# Generador_de_Funciones.net
KiCad netlist of a schematic drawn in EAGLE
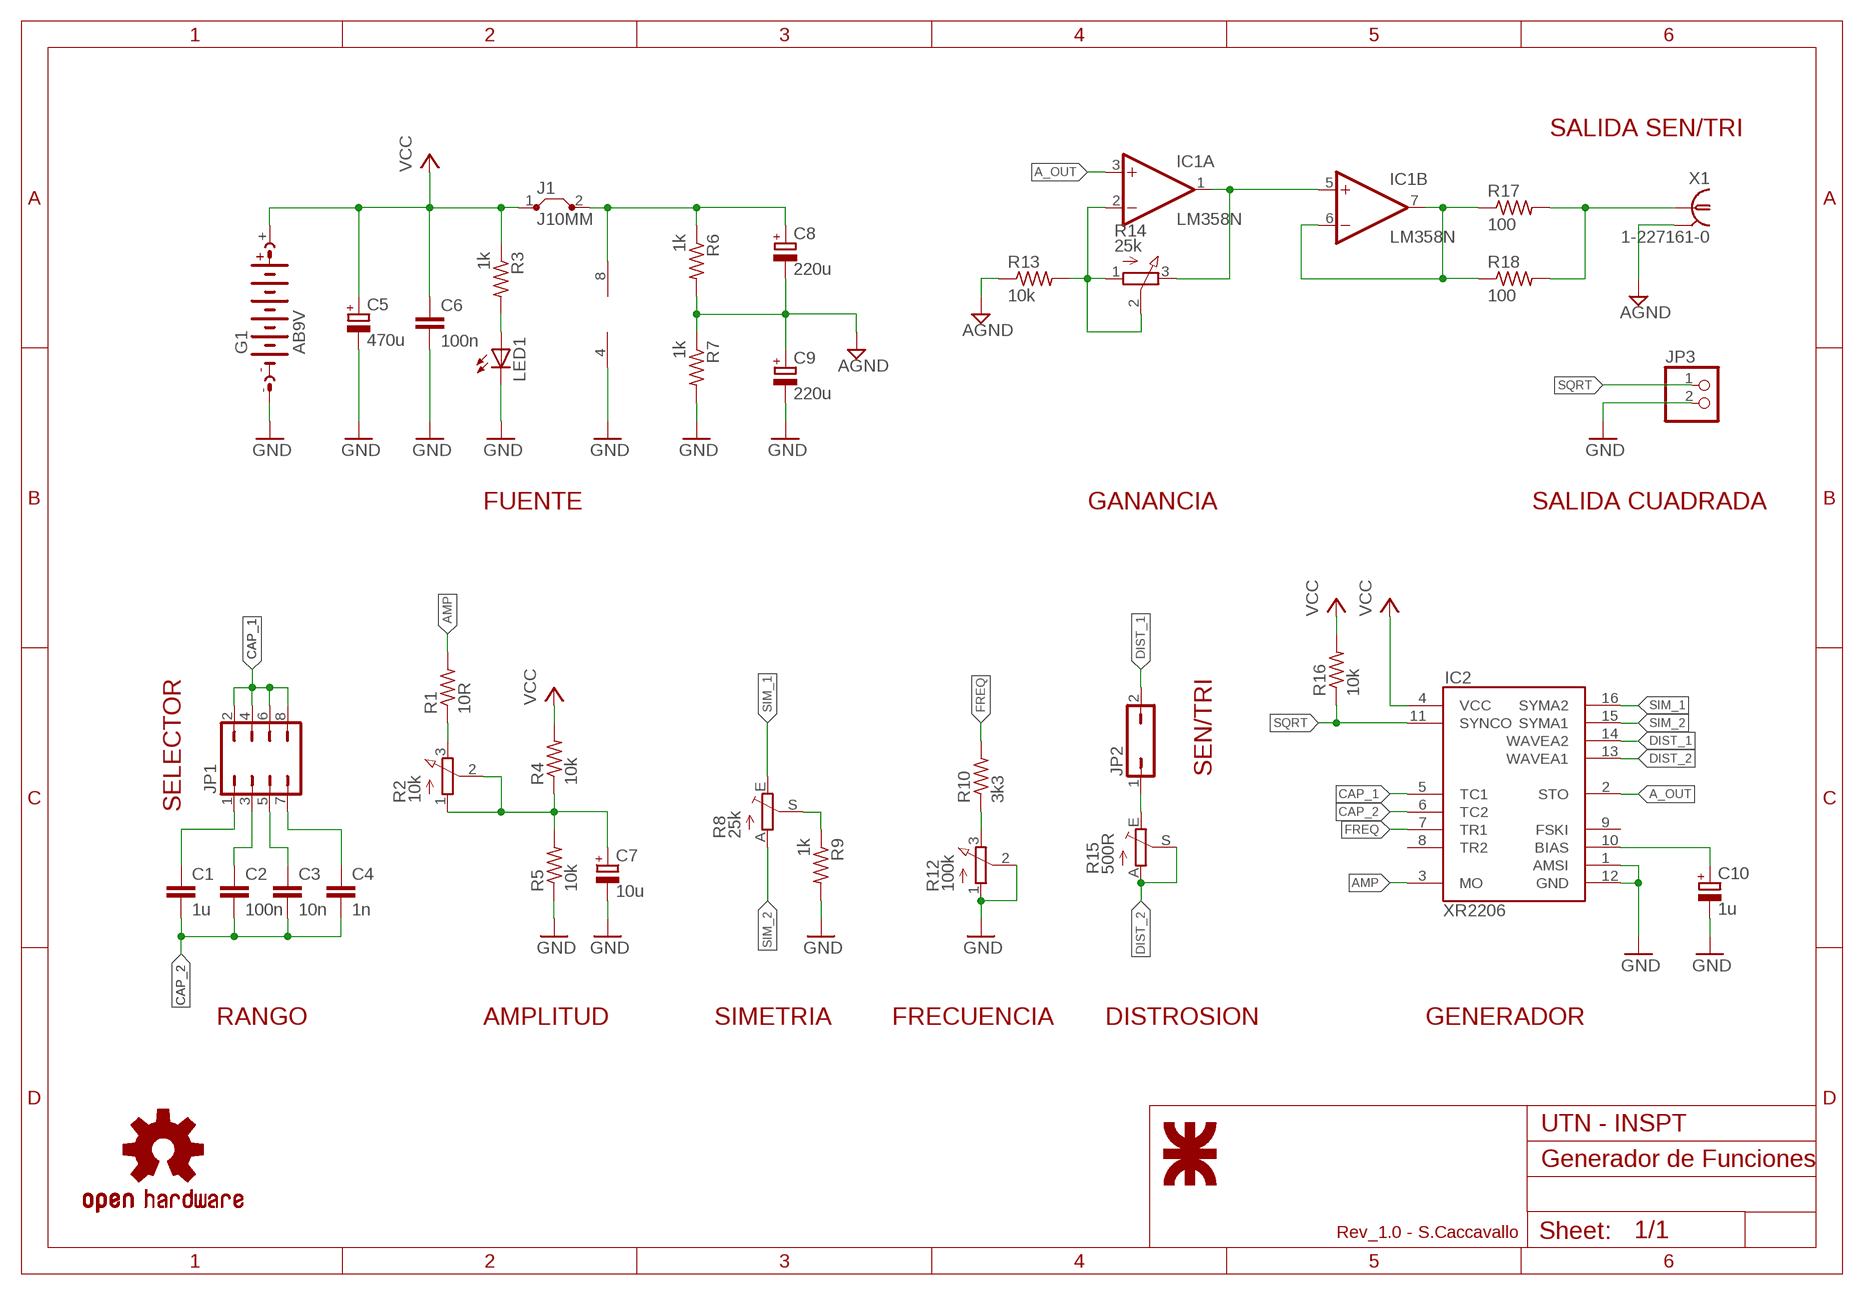
[diagram p0: schematic, sheet 1]

(export (version "E")
  (design (tool "Eeschema 10.0.6"))
  (components
    (comp (ref "C1")
      (value "1u")
      (footprint "eagle-import:C050-024X044")
      (libsource (lib "eagle-import") (part "C-EU050-024X044"))
    )
    (comp (ref "C2")
      (value "100n")
      (footprint "eagle-import:C050-024X044")
      (libsource (lib "eagle-import") (part "C-EU050-024X044"))
    )
    (comp (ref "C3")
      (value "10n")
      (footprint "eagle-import:C050-024X044")
      (libsource (lib "eagle-import") (part "C-EU050-024X044"))
    )
    (comp (ref "C4")
      (value "1n")
      (footprint "eagle-import:C050-024X044")
      (libsource (lib "eagle-import") (part "C-EU050-024X044"))
    )
    (comp (ref "C5")
      (value "470u")
      (footprint "eagle-import:E3,5-8")
      (libsource (lib "eagle-import") (part "CPOL-EUE3.5-8"))
    )
    (comp (ref "C6")
      (value "100n")
      (footprint "eagle-import:C050-024X044")
      (libsource (lib "eagle-import") (part "C-EU050-024X044"))
    )
    (comp (ref "C7")
      (value "10u")
      (footprint "eagle-import:E2,5-6")
      (libsource (lib "eagle-import") (part "CPOL-EUE2.5-6"))
    )
    (comp (ref "C8")
      (value "220u")
      (footprint "eagle-import:E3,5-8")
      (libsource (lib "eagle-import") (part "CPOL-EUE3.5-8"))
    )
    (comp (ref "C9")
      (value "220u")
      (footprint "eagle-import:E3,5-8")
      (libsource (lib "eagle-import") (part "CPOL-EUE3.5-8"))
    )
    (comp (ref "C10")
      (value "1u")
      (footprint "eagle-import:E2,5-6")
      (libsource (lib "eagle-import") (part "CPOL-EUE2.5-6"))
    )
    (comp (ref "G1")
      (value "AB9V")
      (footprint "eagle-import:AB9V")
      (libsource (lib "eagle-import") (part "AB9V"))
    )
    (comp (ref "IC1")
      (value "LM358N")
      (footprint "eagle-import:DIL08")
      (libsource (lib "eagle-import") (part "LM358N"))
    )
    (comp (ref "IC2")
      (value "XR2206")
      (footprint "eagle-import:DIL16")
      (libsource (lib "eagle-import") (part "XR2206"))
    )
    (comp (ref "J1")
      (value "J10MM")
      (footprint "eagle-import:10")
      (libsource (lib "eagle-import") (part "J10MM"))
    )
    (comp (ref "JP1")
      (value "JP4Q")
      (footprint "eagle-import:JP4Q")
      (libsource (lib "eagle-import") (part "JP4Q"))
    )
    (comp (ref "JP2")
      (value "JP1Q")
      (footprint "eagle-import:JP1")
      (libsource (lib "eagle-import") (part "JP1Q"))
    )
    (comp (ref "JP3")
      (value "PINHD-1X2")
      (footprint "eagle-import:1X02")
      (libsource (lib "eagle-import") (part "PINHD-1X2"))
    )
    (comp (ref "LED1")
      (value "LED5MM")
      (footprint "eagle-import:LED5MM")
      (libsource (lib "eagle-import") (part "LED5MM"))
    )
    (comp (ref "R1")
      (value "10R")
      (footprint "eagle-import:0204_7")
      (libsource (lib "eagle-import") (part "R-US_0204/7"))
    )
    (comp (ref "R2")
      (value "10k")
      (footprint "eagle-import:3RP_1610N")
      (libsource (lib "eagle-import") (part "3RP/1610N"))
    )
    (comp (ref "R3")
      (value "1k")
      (footprint "eagle-import:0204_7")
      (libsource (lib "eagle-import") (part "R-US_0204/7"))
    )
    (comp (ref "R4")
      (value "10k")
      (footprint "eagle-import:0204_7")
      (libsource (lib "eagle-import") (part "R-US_0204/7"))
    )
    (comp (ref "R5")
      (value "10k")
      (footprint "eagle-import:0204_7")
      (libsource (lib "eagle-import") (part "R-US_0204/7"))
    )
    (comp (ref "R6")
      (value "1k")
      (footprint "eagle-import:0204_7")
      (libsource (lib "eagle-import") (part "R-US_0204/7"))
    )
    (comp (ref "R7")
      (value "1k")
      (footprint "eagle-import:0204_7")
      (libsource (lib "eagle-import") (part "R-US_0204/7"))
    )
    (comp (ref "R8")
      (value "25k")
      (footprint "eagle-import:RJ9W")
      (libsource (lib "eagle-import") (part "TRIM_EU-RJ9W"))
    )
    (comp (ref "R9")
      (value "1k")
      (footprint "eagle-import:0204_7")
      (libsource (lib "eagle-import") (part "R-US_0204/7"))
    )
    (comp (ref "R10")
      (value "3k3")
      (footprint "eagle-import:0204_7")
      (libsource (lib "eagle-import") (part "R-US_0204/7"))
    )
    (comp (ref "R12")
      (value "100k")
      (footprint "eagle-import:3RP_1610N")
      (libsource (lib "eagle-import") (part "3RP/1610N"))
    )
    (comp (ref "R13")
      (value "10k")
      (footprint "eagle-import:0204_7")
      (libsource (lib "eagle-import") (part "R-US_0204/7"))
    )
    (comp (ref "R14")
      (value "25k")
      (footprint "eagle-import:3RP_1610N")
      (libsource (lib "eagle-import") (part "3RP/1610N"))
    )
    (comp (ref "R15")
      (value "500R")
      (footprint "eagle-import:RJ9W")
      (libsource (lib "eagle-import") (part "TRIM_EU-RJ9W"))
    )
    (comp (ref "R16")
      (value "10k")
      (footprint "eagle-import:0204_7")
      (libsource (lib "eagle-import") (part "R-US_0204/7"))
    )
    (comp (ref "R17")
      (value "100")
      (footprint "eagle-import:0204_7")
      (libsource (lib "eagle-import") (part "R-US_0204/7"))
    )
    (comp (ref "R18")
      (value "100")
      (footprint "eagle-import:0204_7")
      (libsource (lib "eagle-import") (part "R-US_0204/7"))
    )
    (comp (ref "U$1")
      (value "UTN_LOGO_0")
      (footprint "eagle-import:UTN_LOGO_0_TOP")
      (libsource (lib "eagle-import") (part "UTN_LOGO_0"))
    )
    (comp (ref "U$4")
      (value "OSHW-LOGOL")
      (footprint "eagle-import:OSHW-LOGO-L")
      (libsource (lib "eagle-import") (part "OSHW-LOGOL"))
    )
    (comp (ref "X1")
      (value "1-227161-0")
      (footprint "eagle-import:AMP_227161")
      (fields (field (name "MF") "TYCO ELECTRONICS") (field (name "MPN") "1-227161"))
      (libsource (lib "eagle-import") (part "?2271611--0"))
    )
  )
  (nets
    (net (code "1") (name "AGND") (class "Default")
      (node (ref "C8") (pin "-") (pinfunction "-_-") (pintype "passive"))
      (node (ref "C9") (pin "+") (pinfunction "+_+") (pintype "passive"))
      (node (ref "R13") (pin "1") (pinfunction "1_1") (pintype "passive"))
      (node (ref "R6") (pin "2") (pinfunction "2_2") (pintype "passive"))
      (node (ref "R7") (pin "1") (pinfunction "1_1") (pintype "passive"))
      (node (ref "X1") (pin "2") (pinfunction "2_2") (pintype "passive"))
    )
    (net (code "2") (name "AMP") (class "Default")
      (node (ref "IC2") (pin "3") (pinfunction "MO_3") (pintype "output"))
      (node (ref "R1") (pin "2") (pinfunction "2_2") (pintype "passive"))
    )
    (net (code "3") (name "A_OUT") (class "Default")
      (node (ref "IC1") (pin "3") (pinfunction "+IN_3") (pintype "input"))
      (node (ref "IC2") (pin "2") (pinfunction "STO_2") (pintype "output"))
    )
    (net (code "4") (name "CAP_1") (class "Default")
      (node (ref "IC2") (pin "5") (pinfunction "TC1_5") (pintype "input"))
      (node (ref "JP1") (pin "2") (pinfunction "2_2") (pintype "passive"))
      (node (ref "JP1") (pin "4") (pinfunction "4_4") (pintype "passive"))
      (node (ref "JP1") (pin "6") (pinfunction "6_6") (pintype "passive"))
      (node (ref "JP1") (pin "8") (pinfunction "8_8") (pintype "passive"))
    )
    (net (code "5") (name "CAP_2") (class "Default")
      (node (ref "C1") (pin "2") (pinfunction "2_2") (pintype "passive"))
      (node (ref "C2") (pin "2") (pinfunction "2_2") (pintype "passive"))
      (node (ref "C3") (pin "2") (pinfunction "2_2") (pintype "passive"))
      (node (ref "C4") (pin "2") (pinfunction "2_2") (pintype "passive"))
      (node (ref "IC2") (pin "6") (pinfunction "TC2_6") (pintype "input"))
    )
    (net (code "6") (name "DIST_1") (class "Default")
      (node (ref "IC2") (pin "14") (pinfunction "WAVEA2_14") (pintype "input"))
      (node (ref "JP2") (pin "2") (pinfunction "2_2") (pintype "passive"))
    )
    (net (code "7") (name "DIST_2") (class "Default")
      (node (ref "IC2") (pin "13") (pinfunction "WAVEA1_13") (pintype "input"))
      (node (ref "R15") (pin "A") (pinfunction "A_A") (pintype "passive"))
      (node (ref "R15") (pin "S") (pinfunction "S_S") (pintype "passive"))
    )
    (net (code "8") (name "FREQ") (class "Default")
      (node (ref "IC2") (pin "7") (pinfunction "TR1_7") (pintype "output"))
      (node (ref "R10") (pin "2") (pinfunction "2_2") (pintype "passive"))
    )
    (net (code "9") (name "GND") (class "Default")
      (node (ref "C10") (pin "-") (pinfunction "-_-") (pintype "passive"))
      (node (ref "C5") (pin "-") (pinfunction "-_-") (pintype "passive"))
      (node (ref "C6") (pin "2") (pinfunction "2_2") (pintype "passive"))
      (node (ref "C7") (pin "-") (pinfunction "-_-") (pintype "passive"))
      (node (ref "C9") (pin "-") (pinfunction "-_-") (pintype "passive"))
      (node (ref "G1") (pin "-") (pinfunction "-_-") (pintype "passive"))
      (node (ref "IC1") (pin "4") (pinfunction "V-_4") (pintype "power_in"))
      (node (ref "IC2") (pin "1") (pinfunction "AMSI_1") (pintype "input"))
      (node (ref "IC2") (pin "12") (pinfunction "GND_12") (pintype "power_in"))
      (node (ref "JP3") (pin "2") (pinfunction "2_2") (pintype "passive"))
      (node (ref "LED1") (pin "K") (pinfunction "C_K") (pintype "passive"))
      (node (ref "R12") (pin "1") (pinfunction "A_1") (pintype "passive"))
      (node (ref "R12") (pin "2") (pinfunction "S_2") (pintype "passive"))
      (node (ref "R5") (pin "1") (pinfunction "1_1") (pintype "passive"))
      (node (ref "R7") (pin "2") (pinfunction "2_2") (pintype "passive"))
      (node (ref "R9") (pin "2") (pinfunction "2_2") (pintype "passive"))
    )
    (net (code "10") (name "Net-(C1-Pad1)") (class "Default")
      (node (ref "C1") (pin "1") (pinfunction "1_1") (pintype "passive"))
      (node (ref "JP1") (pin "1") (pinfunction "1_1") (pintype "passive"))
    )
    (net (code "11") (name "Net-(C2-Pad1)") (class "Default")
      (node (ref "C2") (pin "1") (pinfunction "1_1") (pintype "passive"))
      (node (ref "JP1") (pin "3") (pinfunction "3_3") (pintype "passive"))
    )
    (net (code "12") (name "Net-(C3-Pad1)") (class "Default")
      (node (ref "C3") (pin "1") (pinfunction "1_1") (pintype "passive"))
      (node (ref "JP1") (pin "5") (pinfunction "5_5") (pintype "passive"))
    )
    (net (code "13") (name "Net-(C4-Pad1)") (class "Default")
      (node (ref "C4") (pin "1") (pinfunction "1_1") (pintype "passive"))
      (node (ref "JP1") (pin "7") (pinfunction "7_7") (pintype "passive"))
    )
    (net (code "14") (name "Net-(IC1A--IN)") (class "Default")
      (node (ref "IC1") (pin "2") (pinfunction "-IN_2") (pintype "input"))
      (node (ref "R13") (pin "2") (pinfunction "2_2") (pintype "passive"))
      (node (ref "R14") (pin "1") (pinfunction "A_1") (pintype "passive"))
      (node (ref "R14") (pin "2") (pinfunction "S_2") (pintype "passive"))
    )
    (net (code "15") (name "Net-(IC1A-OUT)") (class "Default")
      (node (ref "IC1") (pin "1") (pinfunction "OUT_1") (pintype "output"))
      (node (ref "IC1") (pin "5") (pinfunction "+IN_5") (pintype "input"))
      (node (ref "R14") (pin "3") (pinfunction "E_3") (pintype "passive"))
    )
    (net (code "16") (name "Net-(IC1B--IN)") (class "Default")
      (node (ref "IC1") (pin "6") (pinfunction "-IN_6") (pintype "input"))
      (node (ref "IC1") (pin "7") (pinfunction "OUT_7") (pintype "output"))
      (node (ref "R17") (pin "1") (pinfunction "1_1") (pintype "passive"))
      (node (ref "R18") (pin "1") (pinfunction "1_1") (pintype "passive"))
    )
    (net (code "17") (name "Net-(IC1C-V+)") (class "Default")
      (node (ref "C8") (pin "+") (pinfunction "+_+") (pintype "passive"))
      (node (ref "IC1") (pin "8") (pinfunction "V+_8") (pintype "power_in"))
      (node (ref "J1") (pin "2") (pinfunction "2_2") (pintype "passive"))
      (node (ref "R6") (pin "1") (pinfunction "1_1") (pintype "passive"))
    )
    (net (code "18") (name "Net-(IC2-BIAS)") (class "Default")
      (node (ref "C10") (pin "+") (pinfunction "+_+") (pintype "passive"))
      (node (ref "IC2") (pin "10") (pinfunction "BIAS_10") (pintype "output"))
    )
    (net (code "19") (name "Net-(JP2-Pad1)") (class "Default")
      (node (ref "JP2") (pin "1") (pinfunction "1_1") (pintype "passive"))
      (node (ref "R15") (pin "E") (pinfunction "E_E") (pintype "passive"))
    )
    (net (code "20") (name "Net-(LED1-PadA)") (class "Default")
      (node (ref "LED1") (pin "A") (pinfunction "A_A") (pintype "passive"))
      (node (ref "R3") (pin "2") (pinfunction "2_2") (pintype "passive"))
    )
    (net (code "21") (name "Net-(R2-A)") (class "Default")
      (node (ref "C7") (pin "+") (pinfunction "+_+") (pintype "passive"))
      (node (ref "R2") (pin "1") (pinfunction "A_1") (pintype "passive"))
      (node (ref "R2") (pin "2") (pinfunction "S_2") (pintype "passive"))
      (node (ref "R4") (pin "1") (pinfunction "1_1") (pintype "passive"))
      (node (ref "R5") (pin "2") (pinfunction "2_2") (pintype "passive"))
    )
    (net (code "22") (name "Net-(R2-E)") (class "Default")
      (node (ref "R1") (pin "1") (pinfunction "1_1") (pintype "passive"))
      (node (ref "R2") (pin "3") (pinfunction "E_3") (pintype "passive"))
    )
    (net (code "23") (name "Net-(R8-PadS)") (class "Default")
      (node (ref "R8") (pin "S") (pinfunction "S_S") (pintype "passive"))
      (node (ref "R9") (pin "1") (pinfunction "1_1") (pintype "passive"))
    )
    (net (code "24") (name "Net-(R12-E)") (class "Default")
      (node (ref "R10") (pin "1") (pinfunction "1_1") (pintype "passive"))
      (node (ref "R12") (pin "3") (pinfunction "E_3") (pintype "passive"))
    )
    (net (code "25") (name "Net-(R17-Pad2)") (class "Default")
      (node (ref "R17") (pin "2") (pinfunction "2_2") (pintype "passive"))
      (node (ref "R18") (pin "2") (pinfunction "2_2") (pintype "passive"))
      (node (ref "X1") (pin "1") (pinfunction "1_1") (pintype "passive"))
    )
    (net (code "26") (name "SIM_1") (class "Default")
      (node (ref "IC2") (pin "16") (pinfunction "SYMA2_16") (pintype "input"))
      (node (ref "R8") (pin "E") (pinfunction "E_E") (pintype "passive"))
    )
    (net (code "27") (name "SIM_2") (class "Default")
      (node (ref "IC2") (pin "15") (pinfunction "SYMA1_15") (pintype "input"))
      (node (ref "R8") (pin "A") (pinfunction "A_A") (pintype "passive"))
    )
    (net (code "28") (name "SQRT") (class "Default")
      (node (ref "IC2") (pin "11") (pinfunction "SYNCO_11") (pintype "output"))
      (node (ref "JP3") (pin "1") (pinfunction "1_1") (pintype "passive"))
      (node (ref "R16") (pin "1") (pinfunction "1_1") (pintype "passive"))
    )
    (net (code "29") (name "VCC") (class "Default")
      (node (ref "C5") (pin "+") (pinfunction "+_+") (pintype "passive"))
      (node (ref "C6") (pin "1") (pinfunction "1_1") (pintype "passive"))
      (node (ref "G1") (pin "+") (pinfunction "+_+") (pintype "passive"))
      (node (ref "IC2") (pin "4") (pinfunction "VCC_4") (pintype "power_in"))
      (node (ref "J1") (pin "1") (pinfunction "1_1") (pintype "passive"))
      (node (ref "R16") (pin "2") (pinfunction "2_2") (pintype "passive"))
      (node (ref "R3") (pin "1") (pinfunction "1_1") (pintype "passive"))
      (node (ref "R4") (pin "2") (pinfunction "2_2") (pintype "passive"))
    )
    (net (code "30") (name "unconnected-(IC2-FSKI-Pad9)") (class "Default")
      (node (ref "IC2") (pin "9") (pinfunction "FSKI_9") (pintype "input"))
    )
    (net (code "31") (name "unconnected-(IC2-TR2-Pad8)") (class "Default")
      (node (ref "IC2") (pin "8") (pinfunction "TR2_8") (pintype "output"))
    )
  )
)
